# uppsense.net
KiCad netlist of a schematic drawn in Altium Designer
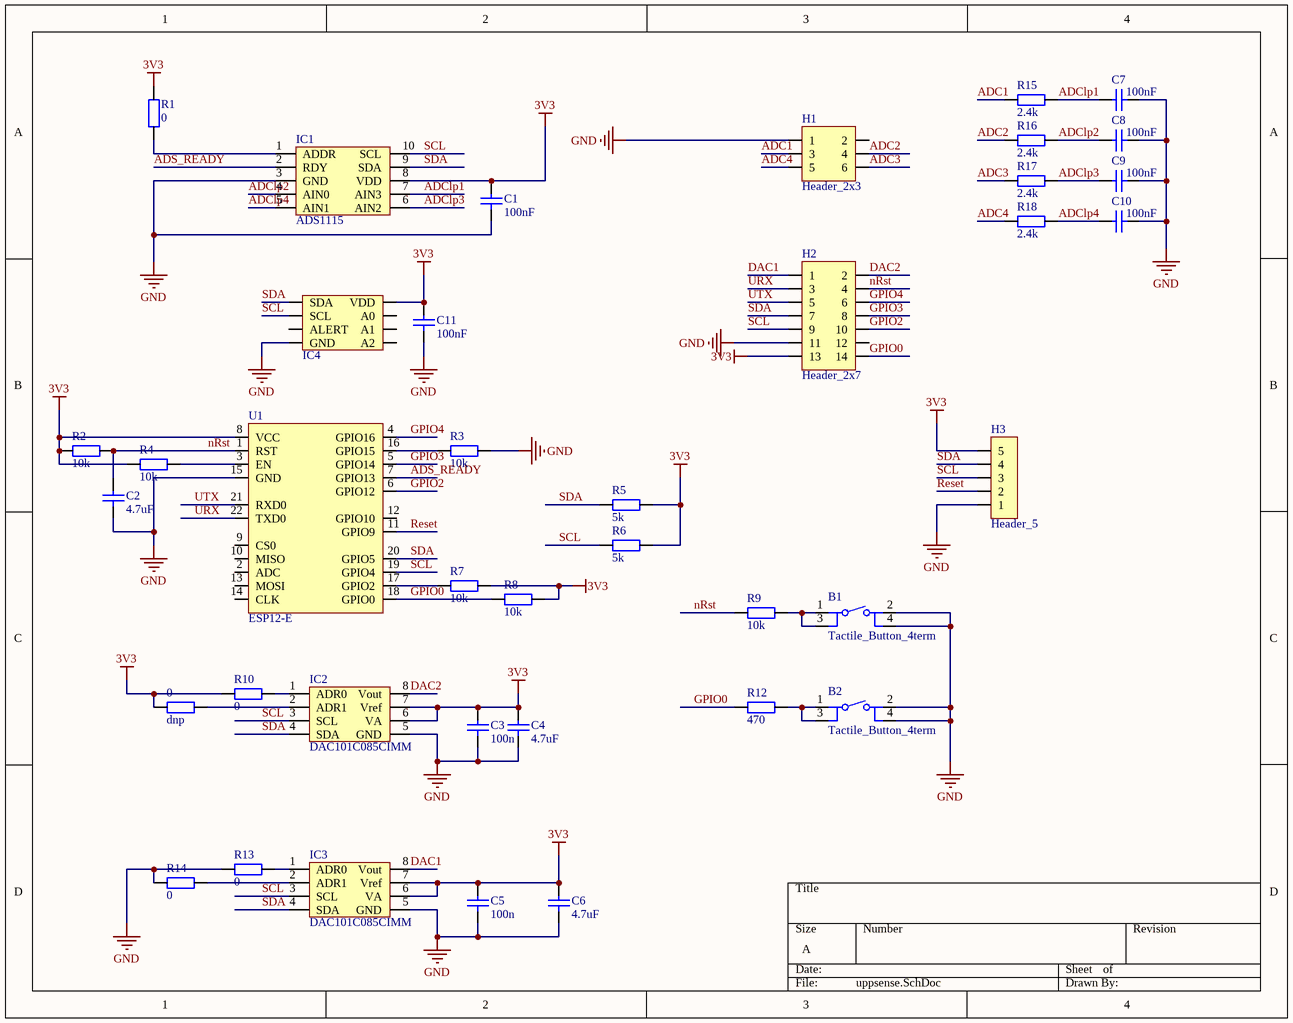
[diagram p0: uppsense.SchDoc]

(export (version "E")
  (design (tool "Eeschema 10.0.6"))
  (components
    (comp (ref "0")
      (value "dnp")
      (footprint "R0603")
      (description "Schematic symbol of a resistor")
      (libsource (lib "AranCustomFootprints") (part "Resistor"))
    )
    (comp (ref "B1")
      (value "Tactile_Button_4term")
      (footprint "TACTILE_MINATUE_SMD_6x6mm")
      (libsource (lib "AranCustomFootprints") (part "Tactile_Button_4term"))
    )
    (comp (ref "B2")
      (value "Tactile_Button_4term")
      (footprint "TACTILE_MINATUE_SMD_6x6mm")
      (libsource (lib "AranCustomFootprints") (part "Tactile_Button_4term"))
    )
    (comp (ref "C1")
      (value "100nF")
      (footprint "C0603")
      (description "Schematic symbol of a capacitor")
      (libsource (lib "AranCustomFootprints") (part "Capacitor"))
    )
    (comp (ref "C2")
      (value "4.7uF")
      (footprint "C0603")
      (description "Schematic symbol of a capacitor")
      (libsource (lib "AranCustomFootprints") (part "Capacitor"))
    )
    (comp (ref "C3")
      (value "100n")
      (footprint "C0603")
      (description "Schematic symbol of a capacitor")
      (libsource (lib "AranCustomFootprints") (part "Capacitor"))
    )
    (comp (ref "C4")
      (value "4.7uF")
      (footprint "C0603")
      (description "Schematic symbol of a capacitor")
      (libsource (lib "AranCustomFootprints") (part "Capacitor"))
    )
    (comp (ref "C5")
      (value "100n")
      (footprint "C0603")
      (description "Schematic symbol of a capacitor")
      (libsource (lib "AranCustomFootprints") (part "Capacitor"))
    )
    (comp (ref "C6")
      (value "4.7uF")
      (footprint "C0603")
      (description "Schematic symbol of a capacitor")
      (libsource (lib "AranCustomFootprints") (part "Capacitor"))
    )
    (comp (ref "C7")
      (value "100nF")
      (footprint "C0603")
      (description "Schematic symbol of a capacitor")
      (libsource (lib "AranCustomFootprints") (part "Capacitor"))
    )
    (comp (ref "C8")
      (value "100nF")
      (footprint "C0603")
      (description "Schematic symbol of a capacitor")
      (libsource (lib "AranCustomFootprints") (part "Capacitor"))
    )
    (comp (ref "C9")
      (value "100nF")
      (footprint "C0603")
      (description "Schematic symbol of a capacitor")
      (libsource (lib "AranCustomFootprints") (part "Capacitor"))
    )
    (comp (ref "C10")
      (value "100nF")
      (footprint "C0603")
      (description "Schematic symbol of a capacitor")
      (libsource (lib "AranCustomFootprints") (part "Capacitor"))
    )
    (comp (ref "C11")
      (value "100nF")
      (footprint "C0603")
      (description "Schematic symbol of a capacitor")
      (libsource (lib "AranCustomFootprints") (part "Capacitor"))
    )
    (comp (ref "H1")
      (value "Header_2x3")
      (footprint "HEADER_MALE_2x3_RIGHT_ANGLE")
      (description "Generic 6pin header symbol")
      (libsource (lib "elmarlib") (part "Header_2x3"))
    )
    (comp (ref "H2")
      (value "Header_2x7")
      (footprint "HEADER_MALE_2x7_RIGHT_ANGLE")
      (description "Generic 14pin header symbol")
      (libsource (lib "elmarlib") (part "Header_2x7"))
    )
    (comp (ref "H3")
      (value "Header_5")
      (footprint "Header_MALE_0.05INCH_5")
      (description "Generic 5pin header symbol")
      (libsource (lib "AranCustomFootprints") (part "Header_5"))
    )
    (comp (ref "IC1")
      (value "ADS1115")
      (footprint "10-VSSOP-0.5")
      (description "ADS111x  Ultra-Small,  Low-Power,  I  2  C-Compatible,  860-SPS,  16-Bit  ADCs")
      (libsource (lib "elmarlib") (part "ADS1115"))
    )
    (comp (ref "IC2")
      (value "DAC101C085CIMM")
      (footprint "8-VSSOP")
      (libsource (lib "elmarlib") (part "DAC101C085CIMM"))
    )
    (comp (ref "IC3")
      (value "DAC101C085CIMM")
      (footprint "8-VSSOP")
      (libsource (lib "elmarlib") (part "DAC101C085CIMM"))
    )
    (comp (ref "IC4")
      (value "MCP9808")
      (footprint "8-MSOP")
      (description "v±0.5°C Maximum Accuracy   Digital Temperature Sensor")
      (libsource (lib "elmarlib") (part "MCP9808"))
    )
    (comp (ref "R1")
      (value "0")
      (footprint "R0603")
      (description "Schematic symbol of a resistor")
      (libsource (lib "AranCustomFootprints") (part "Resistor"))
    )
    (comp (ref "R2")
      (value "10k")
      (footprint "R0603")
      (description "Schematic symbol of a resistor")
      (libsource (lib "AranCustomFootprints") (part "Resistor"))
    )
    (comp (ref "R3")
      (value "10k")
      (footprint "R0603")
      (description "Schematic symbol of a resistor")
      (libsource (lib "AranCustomFootprints") (part "Resistor"))
    )
    (comp (ref "R4")
      (value "10k")
      (footprint "R0603")
      (description "Schematic symbol of a resistor")
      (libsource (lib "AranCustomFootprints") (part "Resistor"))
    )
    (comp (ref "R5")
      (value "5k")
      (footprint "R0603")
      (description "Schematic symbol of a resistor")
      (libsource (lib "AranCustomFootprints") (part "Resistor"))
    )
    (comp (ref "R6")
      (value "5k")
      (footprint "R0603")
      (description "Schematic symbol of a resistor")
      (libsource (lib "AranCustomFootprints") (part "Resistor"))
    )
    (comp (ref "R7")
      (value "10k")
      (footprint "R0603")
      (description "Schematic symbol of a resistor")
      (libsource (lib "AranCustomFootprints") (part "Resistor"))
    )
    (comp (ref "R8")
      (value "10k")
      (footprint "R0603")
      (description "Schematic symbol of a resistor")
      (libsource (lib "AranCustomFootprints") (part "Resistor"))
    )
    (comp (ref "R9")
      (value "10k")
      (footprint "R0603")
      (description "Schematic symbol of a resistor")
      (libsource (lib "AranCustomFootprints") (part "Resistor"))
    )
    (comp (ref "R10")
      (value "0")
      (footprint "R0603")
      (description "Schematic symbol of a resistor")
      (libsource (lib "AranCustomFootprints") (part "Resistor"))
    )
    (comp (ref "R12")
      (value "470")
      (footprint "R0603")
      (description "Schematic symbol of a resistor")
      (libsource (lib "AranCustomFootprints") (part "Resistor"))
    )
    (comp (ref "R13")
      (value "0")
      (footprint "R0603")
      (description "Schematic symbol of a resistor")
      (libsource (lib "AranCustomFootprints") (part "Resistor"))
    )
    (comp (ref "R14")
      (value "0")
      (footprint "R0603")
      (description "Schematic symbol of a resistor")
      (libsource (lib "AranCustomFootprints") (part "Resistor"))
    )
    (comp (ref "R15")
      (value "2.4k")
      (footprint "R0603")
      (description "Schematic symbol of a resistor")
      (libsource (lib "AranCustomFootprints") (part "Resistor"))
    )
    (comp (ref "R16")
      (value "2.4k")
      (footprint "R0603")
      (description "Schematic symbol of a resistor")
      (libsource (lib "AranCustomFootprints") (part "Resistor"))
    )
    (comp (ref "R17")
      (value "2.4k")
      (footprint "R0603")
      (description "Schematic symbol of a resistor")
      (libsource (lib "AranCustomFootprints") (part "Resistor"))
    )
    (comp (ref "R18")
      (value "2.4k")
      (footprint "R0603")
      (description "Schematic symbol of a resistor")
      (libsource (lib "AranCustomFootprints") (part "Resistor"))
    )
    (comp (ref "U1") (value "ESP12-E") (footprint "ESP12-E") (libsource (lib "elmarlib") (part "ESP12-E")))
  )
  (nets
    (net (code "1") (name "/ADC1") (class "Default")
      (node (ref "H1") (pin "3") (pinfunction "3_3") (pintype "passive"))
      (node (ref "R15") (pin "2") (pinfunction "2_2") (pintype "passive"))
    )
    (net (code "2") (name "/ADC2") (class "Default")
      (node (ref "H1") (pin "4") (pinfunction "4_4") (pintype "passive"))
      (node (ref "R16") (pin "2") (pinfunction "2_2") (pintype "passive"))
    )
    (net (code "3") (name "/ADC3") (class "Default")
      (node (ref "H1") (pin "6") (pinfunction "6_6") (pintype "passive"))
      (node (ref "R17") (pin "2") (pinfunction "2_2") (pintype "passive"))
    )
    (net (code "4") (name "/ADC4") (class "Default")
      (node (ref "H1") (pin "5") (pinfunction "5_5") (pintype "passive"))
      (node (ref "R18") (pin "2") (pinfunction "2_2") (pintype "passive"))
    )
    (net (code "5") (name "/ADClp1") (class "Default")
      (node (ref "C7") (pin "1") (pinfunction "1_1") (pintype "passive"))
      (node (ref "IC1") (pin "7") (pinfunction "AIN3_7") (pintype "passive"))
      (node (ref "R15") (pin "1") (pinfunction "1_1") (pintype "passive"))
    )
    (net (code "6") (name "/ADClp2") (class "Default")
      (node (ref "C8") (pin "1") (pinfunction "1_1") (pintype "passive"))
      (node (ref "IC1") (pin "4") (pinfunction "AIN0_4") (pintype "passive"))
      (node (ref "R16") (pin "1") (pinfunction "1_1") (pintype "passive"))
    )
    (net (code "7") (name "/ADClp3") (class "Default")
      (node (ref "C9") (pin "1") (pinfunction "1_1") (pintype "passive"))
      (node (ref "IC1") (pin "6") (pinfunction "AIN2_6") (pintype "passive"))
      (node (ref "R17") (pin "1") (pinfunction "1_1") (pintype "passive"))
    )
    (net (code "8") (name "/ADClp4") (class "Default")
      (node (ref "C10") (pin "1") (pinfunction "1_1") (pintype "passive"))
      (node (ref "IC1") (pin "5") (pinfunction "AIN1_5") (pintype "passive"))
      (node (ref "R18") (pin "1") (pinfunction "1_1") (pintype "passive"))
    )
    (net (code "9") (name "/ADS_READY") (class "Default")
      (node (ref "IC1") (pin "2") (pinfunction "RDY_2") (pintype "passive"))
      (node (ref "U1") (pin "7") (pinfunction "GPIO13_7") (pintype "passive"))
    )
    (net (code "10") (name "/DAC1") (class "Default")
      (node (ref "H2") (pin "1") (pinfunction "1_1") (pintype "passive"))
      (node (ref "IC3") (pin "8") (pinfunction "Vout_8") (pintype "passive"))
    )
    (net (code "11") (name "/DAC2") (class "Default")
      (node (ref "H2") (pin "2") (pinfunction "2_2") (pintype "passive"))
      (node (ref "IC2") (pin "8") (pinfunction "Vout_8") (pintype "passive"))
    )
    (net (code "12") (name "/GPIO0") (class "Default")
      (node (ref "H2") (pin "14") (pinfunction "14_14") (pintype "passive"))
      (node (ref "R12") (pin "2") (pinfunction "2_2") (pintype "passive"))
      (node (ref "R8") (pin "2") (pinfunction "2_2") (pintype "passive"))
      (node (ref "U1") (pin "18") (pinfunction "GPIO0_18") (pintype "passive"))
    )
    (net (code "13") (name "/GPIO2") (class "Default")
      (node (ref "H2") (pin "10") (pinfunction "10_10") (pintype "passive"))
      (node (ref "U1") (pin "6") (pinfunction "GPIO12_6") (pintype "passive"))
    )
    (net (code "14") (name "/GPIO3") (class "Default")
      (node (ref "H2") (pin "8") (pinfunction "8_8") (pintype "passive"))
      (node (ref "U1") (pin "5") (pinfunction "GPIO14_5") (pintype "passive"))
    )
    (net (code "15") (name "/GPIO4") (class "Default")
      (node (ref "H2") (pin "6") (pinfunction "6_6") (pintype "passive"))
      (node (ref "U1") (pin "4") (pinfunction "GPIO16_4") (pintype "passive"))
    )
    (net (code "16") (name "/Reset") (class "Default")
      (node (ref "H3") (pin "2") (pinfunction "2_2") (pintype "passive"))
      (node (ref "U1") (pin "11") (pinfunction "GPIO9_11") (pintype "passive"))
    )
    (net (code "17") (name "/SCL") (class "Default")
      (node (ref "H2") (pin "9") (pinfunction "9_9") (pintype "passive"))
      (node (ref "H3") (pin "3") (pinfunction "3_3") (pintype "passive"))
      (node (ref "IC1") (pin "10") (pinfunction "SCL_10") (pintype "passive"))
      (node (ref "IC2") (pin "3") (pinfunction "SCL_3") (pintype "passive"))
      (node (ref "IC3") (pin "3") (pinfunction "SCL_3") (pintype "passive"))
      (node (ref "IC4") (pin "2") (pinfunction "SCL_2") (pintype "passive"))
      (node (ref "R6") (pin "2") (pinfunction "2_2") (pintype "passive"))
      (node (ref "U1") (pin "19") (pinfunction "GPIO4_19") (pintype "passive"))
    )
    (net (code "18") (name "/SDA") (class "Default")
      (node (ref "H2") (pin "7") (pinfunction "7_7") (pintype "passive"))
      (node (ref "H3") (pin "4") (pinfunction "4_4") (pintype "passive"))
      (node (ref "IC1") (pin "9") (pinfunction "SDA_9") (pintype "passive"))
      (node (ref "IC2") (pin "4") (pinfunction "SDA_4") (pintype "passive"))
      (node (ref "IC3") (pin "4") (pinfunction "SDA_4") (pintype "passive"))
      (node (ref "IC4") (pin "1") (pinfunction "SDA_1") (pintype "passive"))
      (node (ref "R5") (pin "2") (pinfunction "2_2") (pintype "passive"))
      (node (ref "U1") (pin "20") (pinfunction "GPIO5_20") (pintype "passive"))
    )
    (net (code "19") (name "/URX") (class "Default")
      (node (ref "H2") (pin "3") (pinfunction "3_3") (pintype "passive"))
      (node (ref "U1") (pin "22") (pinfunction "TXD0_22") (pintype "passive"))
    )
    (net (code "20") (name "/UTX") (class "Default")
      (node (ref "H2") (pin "5") (pinfunction "5_5") (pintype "passive"))
      (node (ref "U1") (pin "21") (pinfunction "RXD0_21") (pintype "passive"))
    )
    (net (code "21") (name "/nRst") (class "Default")
      (node (ref "C2") (pin "1") (pinfunction "1_1") (pintype "passive"))
      (node (ref "H2") (pin "4") (pinfunction "4_4") (pintype "passive"))
      (node (ref "R2") (pin "1") (pinfunction "1_1") (pintype "passive"))
      (node (ref "R9") (pin "2") (pinfunction "2_2") (pintype "passive"))
      (node (ref "U1") (pin "1") (pinfunction "RST_1") (pintype "passive"))
    )
    (net (code "22") (name "3V3") (class "Default")
      (node (ref "0") (pin "2") (pinfunction "2_2") (pintype "passive"))
      (node (ref "C1") (pin "1") (pinfunction "1_1") (pintype "passive"))
      (node (ref "C11") (pin "1") (pinfunction "1_1") (pintype "passive"))
      (node (ref "C3") (pin "1") (pinfunction "1_1") (pintype "passive"))
      (node (ref "C4") (pin "1") (pinfunction "1_1") (pintype "passive"))
      (node (ref "C5") (pin "1") (pinfunction "1_1") (pintype "passive"))
      (node (ref "C6") (pin "1") (pinfunction "1_1") (pintype "passive"))
      (node (ref "H2") (pin "13") (pinfunction "13_13") (pintype "passive"))
      (node (ref "H3") (pin "5") (pinfunction "5_5") (pintype "passive"))
      (node (ref "IC1") (pin "8") (pinfunction "VDD_8") (pintype "passive"))
      (node (ref "IC2") (pin "6") (pinfunction "VA_6") (pintype "passive"))
      (node (ref "IC2") (pin "7") (pinfunction "Vref_7") (pintype "passive"))
      (node (ref "IC3") (pin "6") (pinfunction "VA_6") (pintype "passive"))
      (node (ref "IC3") (pin "7") (pinfunction "Vref_7") (pintype "passive"))
      (node (ref "IC4") (pin "8") (pinfunction "VDD_8") (pintype "passive"))
      (node (ref "R1") (pin "1") (pinfunction "1_1") (pintype "passive"))
      (node (ref "R10") (pin "2") (pinfunction "2_2") (pintype "passive"))
      (node (ref "R2") (pin "2") (pinfunction "2_2") (pintype "passive"))
      (node (ref "R4") (pin "2") (pinfunction "2_2") (pintype "passive"))
      (node (ref "R5") (pin "1") (pinfunction "1_1") (pintype "passive"))
      (node (ref "R6") (pin "1") (pinfunction "1_1") (pintype "passive"))
      (node (ref "R7") (pin "1") (pinfunction "1_1") (pintype "passive"))
      (node (ref "R8") (pin "1") (pinfunction "1_1") (pintype "passive"))
      (node (ref "U1") (pin "8") (pinfunction "VCC_8") (pintype "passive"))
    )
    (net (code "23") (name "GND") (class "Default")
      (node (ref "B1") (pin "2") (pintype "passive"))
      (node (ref "B1") (pin "4") (pintype "passive"))
      (node (ref "B2") (pin "2") (pintype "passive"))
      (node (ref "B2") (pin "4") (pintype "passive"))
      (node (ref "C1") (pin "2") (pinfunction "2_2") (pintype "passive"))
      (node (ref "C10") (pin "2") (pinfunction "2_2") (pintype "passive"))
      (node (ref "C11") (pin "2") (pinfunction "2_2") (pintype "passive"))
      (node (ref "C2") (pin "2") (pinfunction "2_2") (pintype "passive"))
      (node (ref "C3") (pin "2") (pinfunction "2_2") (pintype "passive"))
      (node (ref "C4") (pin "2") (pinfunction "2_2") (pintype "passive"))
      (node (ref "C5") (pin "2") (pinfunction "2_2") (pintype "passive"))
      (node (ref "C6") (pin "2") (pinfunction "2_2") (pintype "passive"))
      (node (ref "C7") (pin "2") (pinfunction "2_2") (pintype "passive"))
      (node (ref "C8") (pin "2") (pinfunction "2_2") (pintype "passive"))
      (node (ref "C9") (pin "2") (pinfunction "2_2") (pintype "passive"))
      (node (ref "H1") (pin "1") (pinfunction "1_1") (pintype "passive"))
      (node (ref "H2") (pin "11") (pinfunction "11_11") (pintype "passive"))
      (node (ref "H3") (pin "1") (pinfunction "1_1") (pintype "passive"))
      (node (ref "IC1") (pin "3") (pinfunction "GND_3") (pintype "passive"))
      (node (ref "IC2") (pin "5") (pinfunction "GND_5") (pintype "passive"))
      (node (ref "IC3") (pin "5") (pinfunction "GND_5") (pintype "passive"))
      (node (ref "IC4") (pin "4") (pinfunction "GND_4") (pintype "passive"))
      (node (ref "R13") (pin "2") (pinfunction "2_2") (pintype "passive"))
      (node (ref "R14") (pin "2") (pinfunction "2_2") (pintype "passive"))
      (node (ref "R3") (pin "1") (pinfunction "1_1") (pintype "passive"))
      (node (ref "U1") (pin "15") (pinfunction "GND_15") (pintype "passive"))
    )
    (net (code "24") (name "Net-(B1-Pad1)") (class "Default")
      (node (ref "B1") (pin "1") (pintype "passive"))
      (node (ref "B1") (pin "3") (pintype "passive"))
      (node (ref "R9") (pin "1") (pinfunction "1_1") (pintype "passive"))
    )
    (net (code "25") (name "Net-(B2-Pad1)") (class "Default")
      (node (ref "B2") (pin "1") (pintype "passive"))
      (node (ref "B2") (pin "3") (pintype "passive"))
      (node (ref "R12") (pin "1") (pinfunction "1_1") (pintype "passive"))
    )
    (net (code "26") (name "Net-(IC1-ADDR)") (class "Default")
      (node (ref "IC1") (pin "1") (pinfunction "ADDR_1") (pintype "passive"))
      (node (ref "R1") (pin "2") (pinfunction "2_2") (pintype "passive"))
    )
    (net (code "27") (name "Net-(IC2-ADR0)") (class "Default")
      (node (ref "IC2") (pin "1") (pinfunction "ADR0_1") (pintype "passive"))
      (node (ref "R10") (pin "1") (pinfunction "1_1") (pintype "passive"))
    )
    (net (code "28") (name "Net-(IC2-ADR1)") (class "Default")
      (node (ref "0") (pin "1") (pinfunction "1_1") (pintype "passive"))
      (node (ref "IC2") (pin "2") (pinfunction "ADR1_2") (pintype "passive"))
    )
    (net (code "29") (name "Net-(IC3-ADR0)") (class "Default")
      (node (ref "IC3") (pin "1") (pinfunction "ADR0_1") (pintype "passive"))
      (node (ref "R13") (pin "1") (pinfunction "1_1") (pintype "passive"))
    )
    (net (code "30") (name "Net-(IC3-ADR1)") (class "Default")
      (node (ref "IC3") (pin "2") (pinfunction "ADR1_2") (pintype "passive"))
      (node (ref "R14") (pin "1") (pinfunction "1_1") (pintype "passive"))
    )
    (net (code "31") (name "Net-(U1-EN)") (class "Default")
      (node (ref "R4") (pin "1") (pinfunction "1_1") (pintype "passive"))
      (node (ref "U1") (pin "3") (pinfunction "EN_3") (pintype "passive"))
    )
    (net (code "32") (name "Net-(U1-GPIO2)") (class "Default")
      (node (ref "R7") (pin "2") (pinfunction "2_2") (pintype "passive"))
      (node (ref "U1") (pin "17") (pinfunction "GPIO2_17") (pintype "passive"))
    )
    (net (code "33") (name "Net-(U1-GPIO15)") (class "Default")
      (node (ref "R3") (pin "2") (pinfunction "2_2") (pintype "passive"))
      (node (ref "U1") (pin "16") (pinfunction "GPIO15_16") (pintype "passive"))
    )
    (net (code "34") (name "unconnected-(H1-Pad2)") (class "Default")
      (node (ref "H1") (pin "2") (pinfunction "2_2") (pintype "passive"))
    )
    (net (code "35") (name "unconnected-(H2-Pad12)") (class "Default")
      (node (ref "H2") (pin "12") (pinfunction "12_12") (pintype "passive"))
    )
    (net (code "36") (name "unconnected-(IC4-A0-Pad7)") (class "Default")
      (node (ref "IC4") (pin "7") (pinfunction "A0_7") (pintype "passive"))
    )
    (net (code "37") (name "unconnected-(IC4-A1-Pad6)") (class "Default")
      (node (ref "IC4") (pin "6") (pinfunction "A1_6") (pintype "passive"))
    )
    (net (code "38") (name "unconnected-(IC4-A2-Pad5)") (class "Default")
      (node (ref "IC4") (pin "5") (pinfunction "A2_5") (pintype "passive"))
    )
    (net (code "39") (name "unconnected-(IC4-ALERT-Pad3)") (class "Default")
      (node (ref "IC4") (pin "3") (pinfunction "ALERT_3") (pintype "passive"))
    )
    (net (code "40") (name "unconnected-(U1-ADC-Pad2)") (class "Default")
      (node (ref "U1") (pin "2") (pinfunction "ADC_2") (pintype "passive"))
    )
    (net (code "41") (name "unconnected-(U1-CLK-Pad14)") (class "Default")
      (node (ref "U1") (pin "14") (pinfunction "CLK_14") (pintype "passive"))
    )
    (net (code "42") (name "unconnected-(U1-CS0-Pad9)") (class "Default")
      (node (ref "U1") (pin "9") (pinfunction "CS0_9") (pintype "passive"))
    )
    (net (code "43") (name "unconnected-(U1-GPIO10-Pad12)") (class "Default")
      (node (ref "U1") (pin "12") (pinfunction "GPIO10_12") (pintype "passive"))
    )
    (net (code "44") (name "unconnected-(U1-MISO-Pad10)") (class "Default")
      (node (ref "U1") (pin "10") (pinfunction "MISO_10") (pintype "passive"))
    )
    (net (code "45") (name "unconnected-(U1-MOSI-Pad13)") (class "Default")
      (node (ref "U1") (pin "13") (pinfunction "MOSI_13") (pintype "passive"))
    )
  )
)
